# dwm1000addon.net
KiCad netlist of a schematic drawn in EAGLE
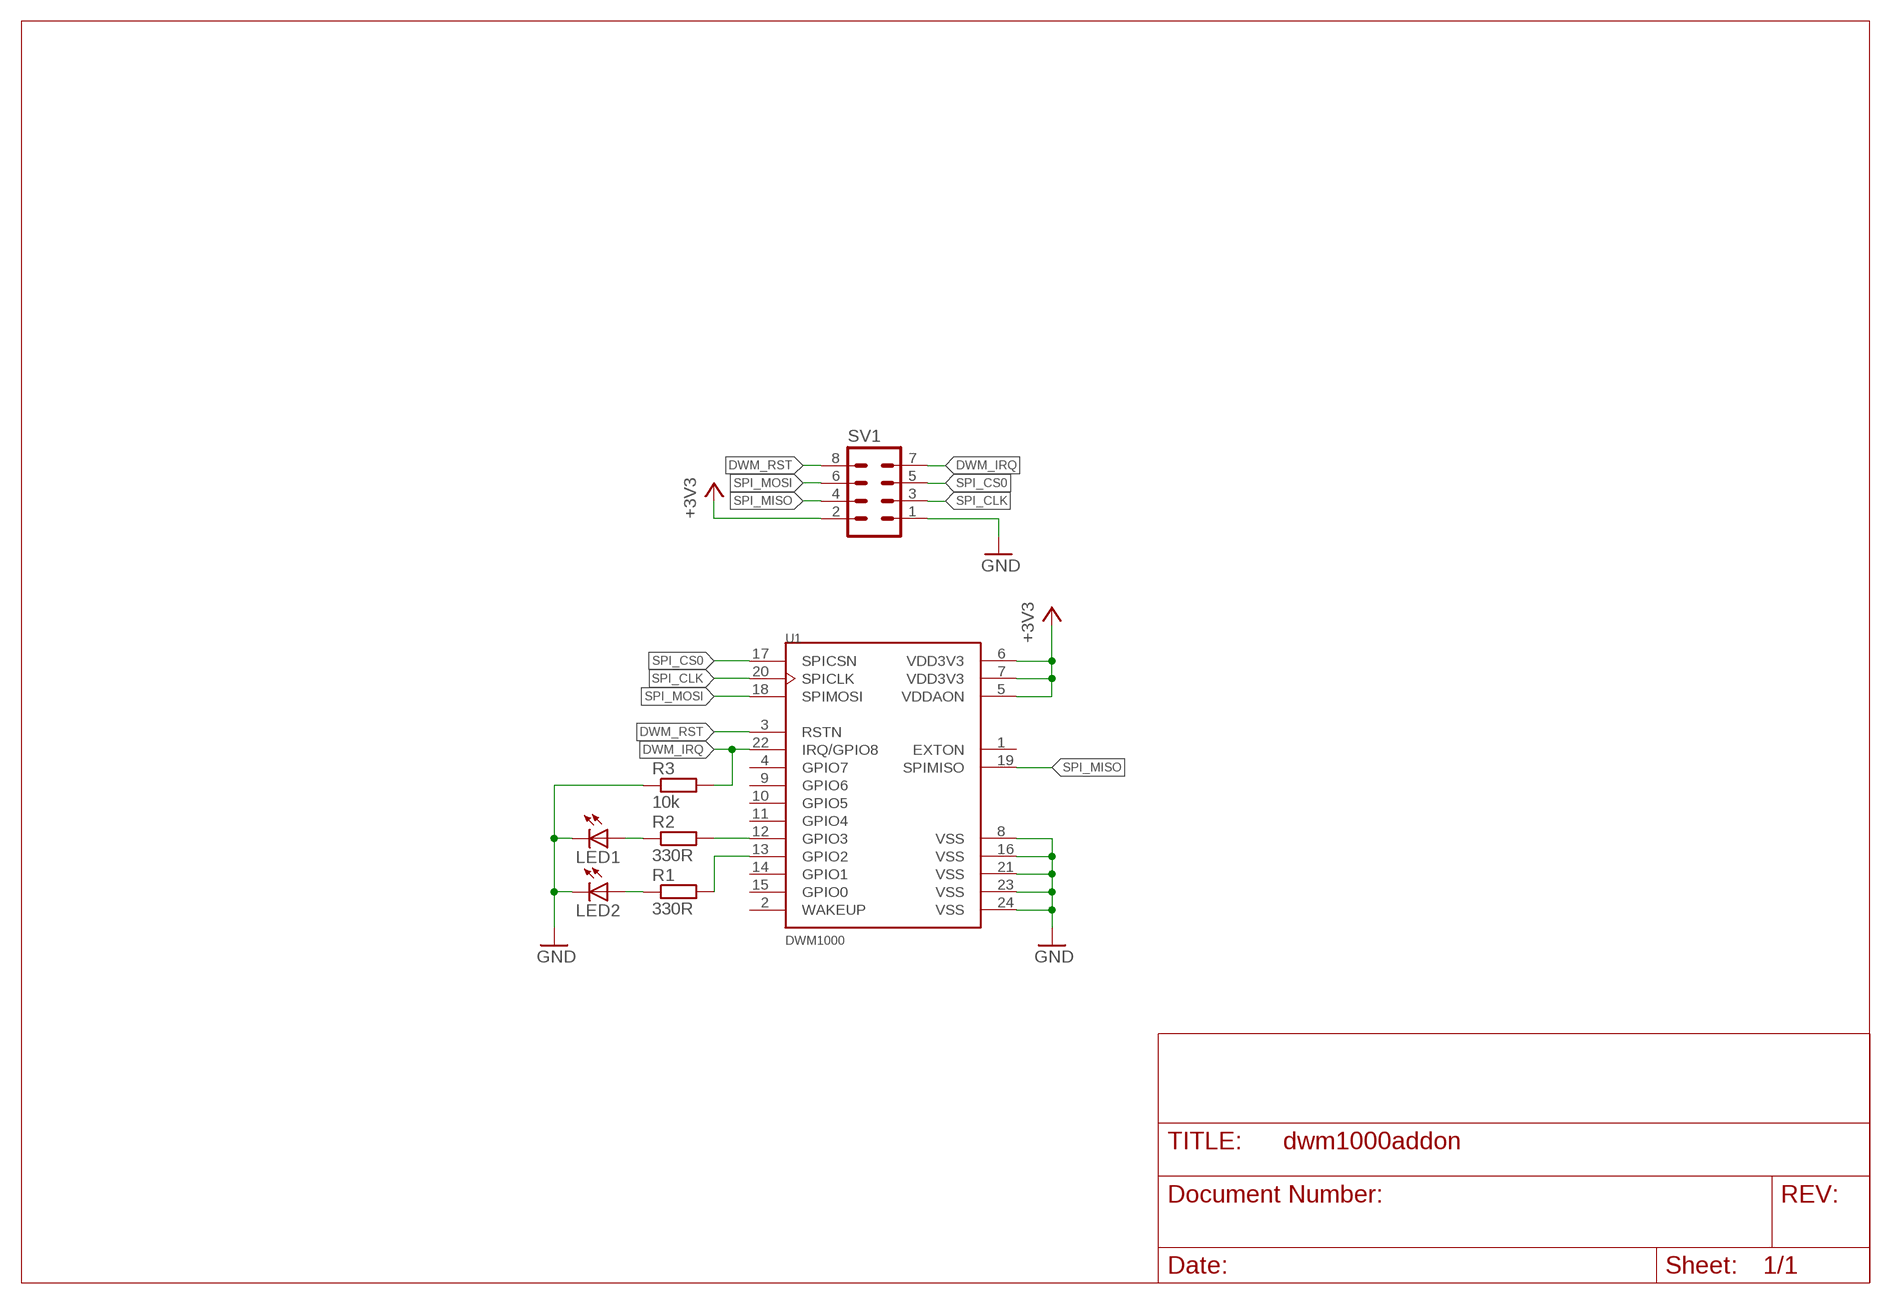
[diagram p0: schematic, sheet 1]

(export (version "E")
  (design (tool "Eeschema 10.0.6"))
  (components
    (comp (ref "LED1")
      (value "LEDCHIPLED_0603")
      (footprint "eagle-import:CHIPLED_0603")
      (libsource (lib "eagle-import") (part "LEDCHIPLED_0603"))
    )
    (comp (ref "LED2")
      (value "LEDCHIPLED_0603")
      (footprint "eagle-import:CHIPLED_0603")
      (libsource (lib "eagle-import") (part "LEDCHIPLED_0603"))
    )
    (comp (ref "R1")
      (value "330R")
      (footprint "eagle-import:R0603")
      (libsource (lib "eagle-import") (part "R-EU_R0603"))
    )
    (comp (ref "R2")
      (value "330R")
      (footprint "eagle-import:R0603")
      (libsource (lib "eagle-import") (part "R-EU_R0603"))
    )
    (comp (ref "R3")
      (value "10k")
      (footprint "eagle-import:R0603")
      (libsource (lib "eagle-import") (part "R-EU_R0603"))
    )
    (comp (ref "SV1")
      (value "MA04-2")
      (footprint "eagle-import:MA04-2")
      (libsource (lib "eagle-import") (part "MA04-2"))
    )
    (comp (ref "U1")
      (value "DWM1000")
      (footprint "eagle-import:XCVR_DWM1000")
      (libsource (lib "eagle-import") (part "DWM1000"))
    )
  )
  (nets
    (net (code "1") (name "+3V3") (class "Default")
      (node (ref "SV1") (pin "2") (pinfunction "2_2") (pintype "passive"))
      (node (ref "U1") (pin "5") (pinfunction "VDDAON_5") (pintype "power_in"))
      (node (ref "U1") (pin "6") (pinfunction "VDD3V3_6") (pintype "power_in"))
      (node (ref "U1") (pin "7") (pinfunction "VDD3V3_7") (pintype "power_in"))
    )
    (net (code "2") (name "DWM_IRQ") (class "Default")
      (node (ref "R3") (pin "2") (pinfunction "2_2") (pintype "passive"))
      (node (ref "SV1") (pin "7") (pinfunction "7_7") (pintype "passive"))
      (node (ref "U1") (pin "22") (pinfunction "IRQ/GPIO8_22") (pintype "bidirectional"))
    )
    (net (code "3") (name "DWM_RST") (class "Default")
      (node (ref "SV1") (pin "8") (pinfunction "8_8") (pintype "passive"))
      (node (ref "U1") (pin "3") (pinfunction "RSTN_3") (pintype "bidirectional"))
    )
    (net (code "4") (name "GND") (class "Default")
      (node (ref "LED1") (pin "C") (pinfunction "C_C") (pintype "passive"))
      (node (ref "LED2") (pin "C") (pinfunction "C_C") (pintype "passive"))
      (node (ref "R3") (pin "1") (pinfunction "1_1") (pintype "passive"))
      (node (ref "SV1") (pin "1") (pinfunction "1_1") (pintype "passive"))
      (node (ref "U1") (pin "16") (pinfunction "VSS_16") (pintype "power_in"))
      (node (ref "U1") (pin "21") (pinfunction "VSS_21") (pintype "power_in"))
      (node (ref "U1") (pin "23") (pinfunction "VSS_23") (pintype "power_in"))
      (node (ref "U1") (pin "24") (pinfunction "VSS_24") (pintype "power_in"))
      (node (ref "U1") (pin "8") (pinfunction "VSS_8") (pintype "power_in"))
    )
    (net (code "5") (name "Net-(LED1-PadA)") (class "Default")
      (node (ref "LED1") (pin "A") (pinfunction "A_A") (pintype "passive"))
      (node (ref "R2") (pin "1") (pinfunction "1_1") (pintype "passive"))
    )
    (net (code "6") (name "Net-(LED2-PadA)") (class "Default")
      (node (ref "LED2") (pin "A") (pinfunction "A_A") (pintype "passive"))
      (node (ref "R1") (pin "1") (pinfunction "1_1") (pintype "passive"))
    )
    (net (code "7") (name "Net-(U1-GPIO2)") (class "Default")
      (node (ref "R1") (pin "2") (pinfunction "2_2") (pintype "passive"))
      (node (ref "U1") (pin "13") (pinfunction "GPIO2_13") (pintype "bidirectional"))
    )
    (net (code "8") (name "Net-(U1-GPIO3)") (class "Default")
      (node (ref "R2") (pin "2") (pinfunction "2_2") (pintype "passive"))
      (node (ref "U1") (pin "12") (pinfunction "GPIO3_12") (pintype "bidirectional"))
    )
    (net (code "9") (name "SPI_CLK") (class "Default")
      (node (ref "SV1") (pin "3") (pinfunction "3_3") (pintype "passive"))
      (node (ref "U1") (pin "20") (pinfunction "SPICLK_20") (pintype "input"))
    )
    (net (code "10") (name "SPI_CS0") (class "Default")
      (node (ref "SV1") (pin "5") (pinfunction "5_5") (pintype "passive"))
      (node (ref "U1") (pin "17") (pinfunction "SPICSN_17") (pintype "input"))
    )
    (net (code "11") (name "SPI_MISO") (class "Default")
      (node (ref "SV1") (pin "4") (pinfunction "4_4") (pintype "passive"))
      (node (ref "U1") (pin "19") (pinfunction "SPIMISO_19") (pintype "output"))
    )
    (net (code "12") (name "SPI_MOSI") (class "Default")
      (node (ref "SV1") (pin "6") (pinfunction "6_6") (pintype "passive"))
      (node (ref "U1") (pin "18") (pinfunction "SPIMOSI_18") (pintype "input"))
    )
    (net (code "13") (name "unconnected-(U1-EXTON-Pad1)") (class "Default")
      (node (ref "U1") (pin "1") (pinfunction "EXTON_1") (pintype "output"))
    )
    (net (code "14") (name "unconnected-(U1-GPIO0-Pad15)") (class "Default")
      (node (ref "U1") (pin "15") (pinfunction "GPIO0_15") (pintype "bidirectional"))
    )
    (net (code "15") (name "unconnected-(U1-GPIO1-Pad14)") (class "Default")
      (node (ref "U1") (pin "14") (pinfunction "GPIO1_14") (pintype "bidirectional"))
    )
    (net (code "16") (name "unconnected-(U1-GPIO4-Pad11)") (class "Default")
      (node (ref "U1") (pin "11") (pinfunction "GPIO4_11") (pintype "bidirectional"))
    )
    (net (code "17") (name "unconnected-(U1-GPIO5-Pad10)") (class "Default")
      (node (ref "U1") (pin "10") (pinfunction "GPIO5_10") (pintype "bidirectional"))
    )
    (net (code "18") (name "unconnected-(U1-GPIO6-Pad9)") (class "Default")
      (node (ref "U1") (pin "9") (pinfunction "GPIO6_9") (pintype "bidirectional"))
    )
    (net (code "19") (name "unconnected-(U1-GPIO7-Pad4)") (class "Default")
      (node (ref "U1") (pin "4") (pinfunction "GPIO7_4") (pintype "bidirectional"))
    )
    (net (code "20") (name "unconnected-(U1-WAKEUP-Pad2)") (class "Default")
      (node (ref "U1") (pin "2") (pinfunction "WAKEUP_2") (pintype "bidirectional"))
    )
  )
)
